# Sheet3.net
KiCad netlist of a schematic drawn in Altium Designer
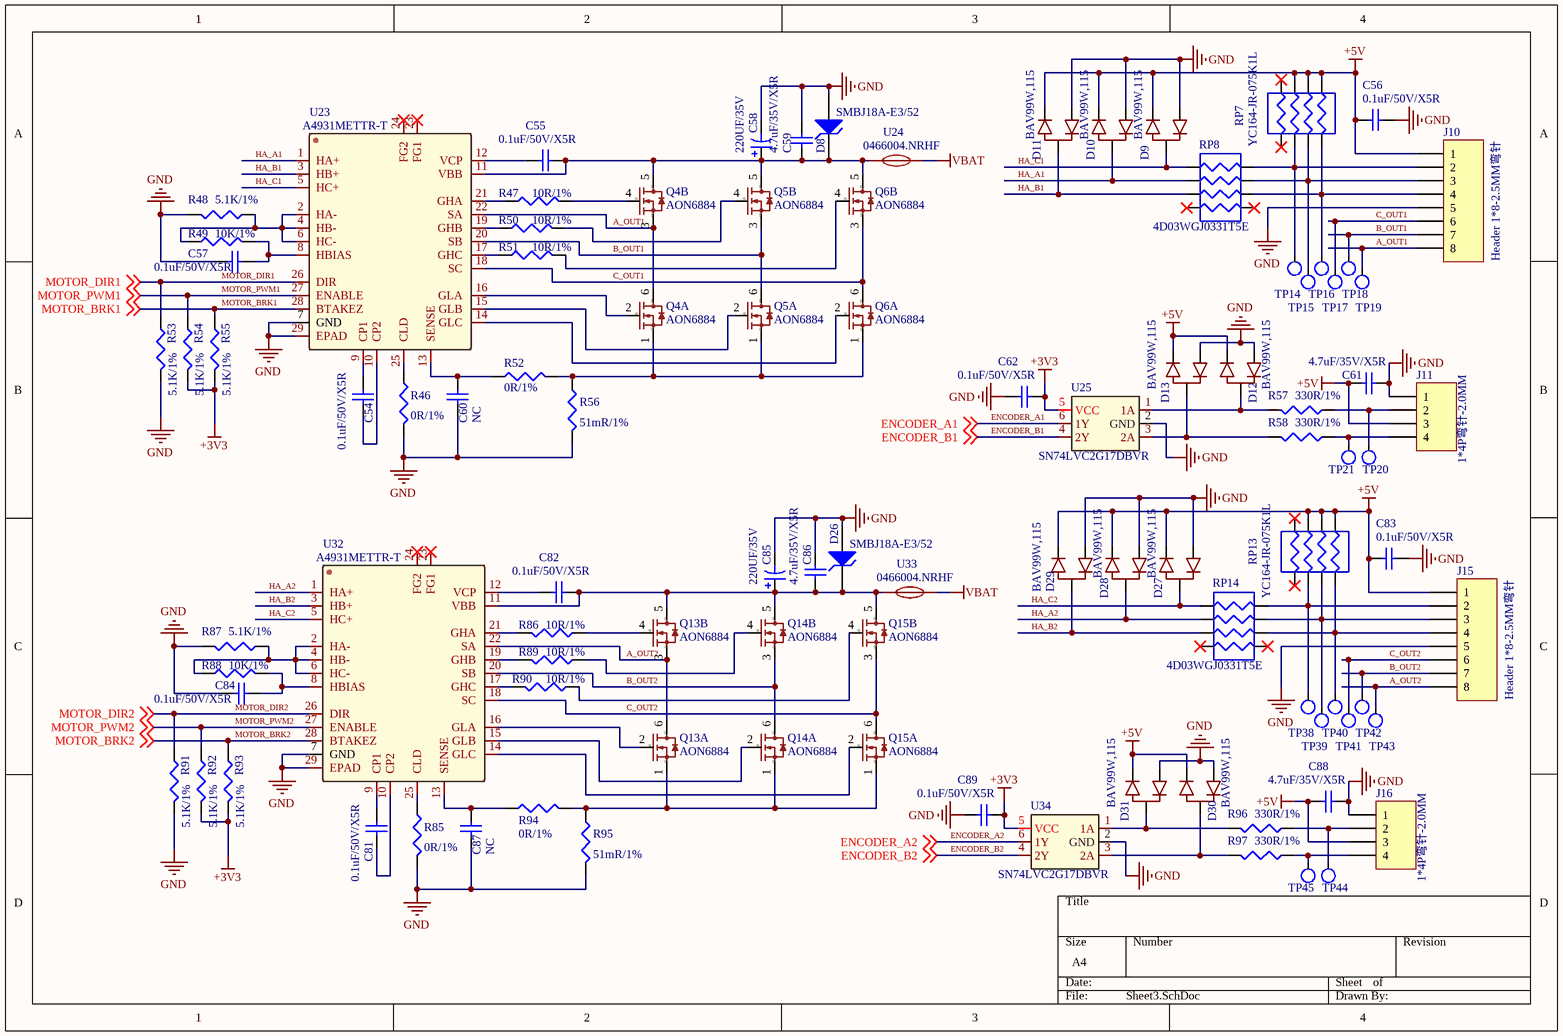
[diagram p0: Sheet3.SchDoc]

(export (version "E")
  (design (tool "Eeschema 10.0.6"))
  (components
    (comp (ref "C54")
      (value "0.1uF/50V/X5R")
      (footprint "C0603")
      (description "Capacitor (Semiconductor SIM Model)")
      (fields (field (name "PUBLISHER") "Altium Limited"))
      (libsource (lib "Miscellaneous Devices") (part "Cap Semi"))
    )
    (comp (ref "C55")
      (value "0.1uF/50V/X5R")
      (footprint "C0603")
      (description "Capacitor (Semiconductor SIM Model)")
      (fields (field (name "PUBLISHER") "Altium Limited"))
      (libsource (lib "Miscellaneous Devices") (part "Cap Semi"))
    )
    (comp (ref "C56")
      (value "0.1uF/50V/X5R")
      (footprint "C0603")
      (description "Capacitor (Semiconductor SIM Model)")
      (fields (field (name "PUBLISHER") "Altium Limited"))
      (libsource (lib "Miscellaneous Devices") (part "Cap Semi"))
    )
    (comp (ref "C57")
      (value "0.1uF/50V/X5R")
      (footprint "C0603")
      (description "Capacitor (Semiconductor SIM Model)")
      (fields (field (name "PUBLISHER") "Altium Limited"))
      (libsource (lib "Miscellaneous Devices") (part "Cap Semi"))
    )
    (comp (ref "C58")
      (value "220UF/35V")
      (footprint "SMD_8X10.2")
      (description "Polarized Capacitor (Radial)")
      (fields (field (name "PUBLISHER") "Altium Limited"))
      (libsource (lib "Miscellaneous Devices") (part "Cap Pol1"))
    )
    (comp (ref "C59")
      (value "4.7uF/35V/X5R")
      (footprint "C0805")
      (description "Capacitor (Semiconductor SIM Model)")
      (fields (field (name "PUBLISHER") "Altium Limited"))
      (libsource (lib "Miscellaneous Devices") (part "Cap Semi"))
    )
    (comp (ref "C60")
      (value "NC")
      (footprint "C0603")
      (description "Capacitor (Semiconductor SIM Model)")
      (fields (field (name "PUBLISHER") "Altium Limited"))
      (libsource (lib "Miscellaneous Devices") (part "Cap Semi"))
    )
    (comp (ref "C61")
      (value "4.7uF/35V/X5R")
      (footprint "C0603")
      (description "Capacitor (Semiconductor SIM Model)")
      (fields (field (name "PUBLISHER") "Altium Limited"))
      (libsource (lib "Miscellaneous Devices") (part "Cap Semi"))
    )
    (comp (ref "C62")
      (value "0.1uF/50V/X5R")
      (footprint "C0603")
      (description "Capacitor (Semiconductor SIM Model)")
      (fields (field (name "PUBLISHER") "Altium Limited"))
      (libsource (lib "Miscellaneous Devices") (part "Cap Semi"))
    )
    (comp (ref "C81")
      (value "0.1uF/50V/X5R")
      (footprint "C0603")
      (description "Capacitor (Semiconductor SIM Model)")
      (fields (field (name "PUBLISHER") "Altium Limited"))
      (libsource (lib "Miscellaneous Devices") (part "Cap Semi"))
    )
    (comp (ref "C82")
      (value "0.1uF/50V/X5R")
      (footprint "C0603")
      (description "Capacitor (Semiconductor SIM Model)")
      (fields (field (name "PUBLISHER") "Altium Limited"))
      (libsource (lib "Miscellaneous Devices") (part "Cap Semi"))
    )
    (comp (ref "C83")
      (value "0.1uF/50V/X5R")
      (footprint "C0603")
      (description "Capacitor (Semiconductor SIM Model)")
      (fields (field (name "PUBLISHER") "Altium Limited"))
      (libsource (lib "Miscellaneous Devices") (part "Cap Semi"))
    )
    (comp (ref "C84")
      (value "0.1uF/50V/X5R")
      (footprint "C0603")
      (description "Capacitor (Semiconductor SIM Model)")
      (fields (field (name "PUBLISHER") "Altium Limited"))
      (libsource (lib "Miscellaneous Devices") (part "Cap Semi"))
    )
    (comp (ref "C85")
      (value "220UF/35V")
      (footprint "SMD_8X10.2")
      (description "Polarized Capacitor (Radial)")
      (fields (field (name "PUBLISHER") "Altium Limited"))
      (libsource (lib "Miscellaneous Devices") (part "Cap Pol1"))
    )
    (comp (ref "C86")
      (value "4.7uF/35V/X5R")
      (footprint "C0805")
      (description "Capacitor (Semiconductor SIM Model)")
      (fields (field (name "PUBLISHER") "Altium Limited"))
      (libsource (lib "Miscellaneous Devices") (part "Cap Semi"))
    )
    (comp (ref "C87")
      (value "NC")
      (footprint "C0603")
      (description "Capacitor (Semiconductor SIM Model)")
      (fields (field (name "PUBLISHER") "Altium Limited"))
      (libsource (lib "Miscellaneous Devices") (part "Cap Semi"))
    )
    (comp (ref "C88")
      (value "4.7uF/35V/X5R")
      (footprint "C0603")
      (description "Capacitor (Semiconductor SIM Model)")
      (fields (field (name "PUBLISHER") "Altium Limited"))
      (libsource (lib "Miscellaneous Devices") (part "Cap Semi"))
    )
    (comp (ref "C89")
      (value "0.1uF/50V/X5R")
      (footprint "C0603")
      (description "Capacitor (Semiconductor SIM Model)")
      (fields (field (name "PUBLISHER") "Altium Limited"))
      (libsource (lib "Miscellaneous Devices") (part "Cap Semi"))
    )
    (comp (ref "D8")
      (value "SMBJ18A-E3/52")
      (footprint "SMB")
      (description "Zener Diode")
      (fields (field (name "PUBLISHER") "Altium Limited"))
      (libsource (lib "Miscellaneous Devices") (part "D Zener"))
    )
    (comp (ref "D9") (value "BAV99W,115") (libsource (lib "Schlib1") (part "BAV99W,115")))
    (comp (ref "D10") (value "BAV99W,115") (libsource (lib "Schlib1") (part "BAV99W,115")))
    (comp (ref "D11") (value "BAV99W,115") (libsource (lib "Schlib1") (part "BAV99W,115")))
    (comp (ref "D12") (value "BAV99W,115") (libsource (lib "Schlib1") (part "BAV99W,115")))
    (comp (ref "D13") (value "BAV99W,115") (libsource (lib "Schlib1") (part "BAV99W,115")))
    (comp (ref "D26")
      (value "SMBJ18A-E3/52")
      (footprint "SMB")
      (description "Zener Diode")
      (fields (field (name "PUBLISHER") "Altium Limited"))
      (libsource (lib "Miscellaneous Devices") (part "D Zener"))
    )
    (comp (ref "D27") (value "BAV99W,115") (libsource (lib "Schlib1") (part "BAV99W,115")))
    (comp (ref "D28") (value "BAV99W,115") (libsource (lib "Schlib1") (part "BAV99W,115")))
    (comp (ref "D29") (value "BAV99W,115") (libsource (lib "Schlib1") (part "BAV99W,115")))
    (comp (ref "D30") (value "BAV99W,115") (libsource (lib "Schlib1") (part "BAV99W,115")))
    (comp (ref "D31") (value "BAV99W,115") (libsource (lib "Schlib1") (part "BAV99W,115")))
    (comp (ref "J10")
      (value "Header 1*8-2.5MM弯针")
      (footprint "DIP_8X2.5")
      (description "Header, 8-Pin")
      (fields (field (name "PUBLISHER") "Altium Limited"))
      (libsource (lib "Miscellaneous Connectors") (part "Header 8"))
    )
    (comp (ref "J11")
      (value "1*4P弯针-2.0MM")
      (footprint "DIP_4X2MM")
      (description "Header, 4-Pin")
      (fields (field (name "PUBLISHER") "Altium Limited"))
      (libsource (lib "Miscellaneous Connectors") (part "Header 4"))
    )
    (comp (ref "J15")
      (value "Header 1*8-2.5MM弯针")
      (footprint "DIP_8X2.5")
      (description "Header, 8-Pin")
      (fields (field (name "PUBLISHER") "Altium Limited"))
      (libsource (lib "Miscellaneous Connectors") (part "Header 8"))
    )
    (comp (ref "J16")
      (value "1*4P弯针-2.0MM")
      (footprint "DIP_4X2MM")
      (description "Header, 4-Pin")
      (fields (field (name "PUBLISHER") "Altium Limited"))
      (libsource (lib "Miscellaneous Connectors") (part "Header 4"))
    )
    (comp (ref "Q4") (value "AON6884") (footprint "AOS") (libsource (lib "Schlib1") (part "AON6884")))
    (comp (ref "Q5") (value "AON6884") (footprint "AOS") (libsource (lib "Schlib1") (part "AON6884")))
    (comp (ref "Q6") (value "AON6884") (footprint "AOS") (libsource (lib "Schlib1") (part "AON6884")))
    (comp (ref "Q13") (value "AON6884") (footprint "AOS") (libsource (lib "Schlib1") (part "AON6884")))
    (comp (ref "Q14") (value "AON6884") (footprint "AOS") (libsource (lib "Schlib1") (part "AON6884")))
    (comp (ref "Q15") (value "AON6884") (footprint "AOS") (libsource (lib "Schlib1") (part "AON6884")))
    (comp (ref "R46")
      (value "0R/1%")
      (footprint "R0603")
      (description "Resistor")
      (fields (field (name "PUBLISHER") "Altium Limited"))
      (libsource (lib "Miscellaneous Devices") (part "Res3"))
    )
    (comp (ref "R47")
      (value "10R/1%")
      (footprint "R0603")
      (description "Resistor")
      (fields (field (name "PUBLISHER") "Altium Limited"))
      (libsource (lib "Miscellaneous Devices") (part "Res3"))
    )
    (comp (ref "R48")
      (value "5.1K/1%")
      (footprint "R0603")
      (description "Resistor")
      (fields (field (name "PUBLISHER") "Altium Limited"))
      (libsource (lib "Miscellaneous Devices") (part "Res3"))
    )
    (comp (ref "R49")
      (value "10K/1%")
      (footprint "R0603")
      (description "Resistor")
      (fields (field (name "PUBLISHER") "Altium Limited"))
      (libsource (lib "Miscellaneous Devices") (part "Res3"))
    )
    (comp (ref "R50")
      (value "10R/1%")
      (footprint "R0603")
      (description "Resistor")
      (fields (field (name "PUBLISHER") "Altium Limited"))
      (libsource (lib "Miscellaneous Devices") (part "Res3"))
    )
    (comp (ref "R51")
      (value "10R/1%")
      (footprint "R0603")
      (description "Resistor")
      (fields (field (name "PUBLISHER") "Altium Limited"))
      (libsource (lib "Miscellaneous Devices") (part "Res3"))
    )
    (comp (ref "R52")
      (value "0R/1%")
      (footprint "R0603")
      (description "Resistor")
      (fields (field (name "PUBLISHER") "Altium Limited"))
      (libsource (lib "Miscellaneous Devices") (part "Res3"))
    )
    (comp (ref "R53")
      (value "5.1K/1%")
      (footprint "R0603")
      (description "Resistor")
      (fields (field (name "PUBLISHER") "Altium Limited"))
      (libsource (lib "Miscellaneous Devices") (part "Res3"))
    )
    (comp (ref "R54")
      (value "5.1K/1%")
      (footprint "R0603")
      (description "Resistor")
      (fields (field (name "PUBLISHER") "Altium Limited"))
      (libsource (lib "Miscellaneous Devices") (part "Res3"))
    )
    (comp (ref "R55")
      (value "5.1K/1%")
      (footprint "R0603")
      (description "Resistor")
      (fields (field (name "PUBLISHER") "Altium Limited"))
      (libsource (lib "Miscellaneous Devices") (part "Res3"))
    )
    (comp (ref "R56")
      (value "51mR/1%")
      (footprint "R0805")
      (description "Resistor")
      (fields (field (name "PUBLISHER") "Altium Limited"))
      (libsource (lib "Miscellaneous Devices") (part "Res3"))
    )
    (comp (ref "R57")
      (value "330R/1%")
      (footprint "R0603")
      (description "Resistor")
      (fields (field (name "PUBLISHER") "Altium Limited"))
      (libsource (lib "Miscellaneous Devices") (part "Res3"))
    )
    (comp (ref "R58")
      (value "330R/1%")
      (footprint "R0603")
      (description "Resistor")
      (fields (field (name "PUBLISHER") "Altium Limited"))
      (libsource (lib "Miscellaneous Devices") (part "Res3"))
    )
    (comp (ref "R85")
      (value "0R/1%")
      (footprint "R0603")
      (description "Resistor")
      (fields (field (name "PUBLISHER") "Altium Limited"))
      (libsource (lib "Miscellaneous Devices") (part "Res3"))
    )
    (comp (ref "R86")
      (value "10R/1%")
      (footprint "R0603")
      (description "Resistor")
      (fields (field (name "PUBLISHER") "Altium Limited"))
      (libsource (lib "Miscellaneous Devices") (part "Res3"))
    )
    (comp (ref "R87")
      (value "5.1K/1%")
      (footprint "R0603")
      (description "Resistor")
      (fields (field (name "PUBLISHER") "Altium Limited"))
      (libsource (lib "Miscellaneous Devices") (part "Res3"))
    )
    (comp (ref "R88")
      (value "10K/1%")
      (footprint "R0603")
      (description "Resistor")
      (fields (field (name "PUBLISHER") "Altium Limited"))
      (libsource (lib "Miscellaneous Devices") (part "Res3"))
    )
    (comp (ref "R89")
      (value "10R/1%")
      (footprint "R0603")
      (description "Resistor")
      (fields (field (name "PUBLISHER") "Altium Limited"))
      (libsource (lib "Miscellaneous Devices") (part "Res3"))
    )
    (comp (ref "R90")
      (value "10R/1%")
      (footprint "R0603")
      (description "Resistor")
      (fields (field (name "PUBLISHER") "Altium Limited"))
      (libsource (lib "Miscellaneous Devices") (part "Res3"))
    )
    (comp (ref "R91")
      (value "5.1K/1%")
      (footprint "R0603")
      (description "Resistor")
      (fields (field (name "PUBLISHER") "Altium Limited"))
      (libsource (lib "Miscellaneous Devices") (part "Res3"))
    )
    (comp (ref "R92")
      (value "5.1K/1%")
      (footprint "R0603")
      (description "Resistor")
      (fields (field (name "PUBLISHER") "Altium Limited"))
      (libsource (lib "Miscellaneous Devices") (part "Res3"))
    )
    (comp (ref "R93")
      (value "5.1K/1%")
      (footprint "R0603")
      (description "Resistor")
      (fields (field (name "PUBLISHER") "Altium Limited"))
      (libsource (lib "Miscellaneous Devices") (part "Res3"))
    )
    (comp (ref "R94")
      (value "0R/1%")
      (footprint "R0603")
      (description "Resistor")
      (fields (field (name "PUBLISHER") "Altium Limited"))
      (libsource (lib "Miscellaneous Devices") (part "Res3"))
    )
    (comp (ref "R95")
      (value "51mR/1%")
      (footprint "R0805")
      (description "Resistor")
      (fields (field (name "PUBLISHER") "Altium Limited"))
      (libsource (lib "Miscellaneous Devices") (part "Res3"))
    )
    (comp (ref "R96")
      (value "330R/1%")
      (footprint "R0603")
      (description "Resistor")
      (fields (field (name "PUBLISHER") "Altium Limited"))
      (libsource (lib "Miscellaneous Devices") (part "Res3"))
    )
    (comp (ref "R97")
      (value "330R/1%")
      (footprint "R0603")
      (description "Resistor")
      (fields (field (name "PUBLISHER") "Altium Limited"))
      (libsource (lib "Miscellaneous Devices") (part "Res3"))
    )
    (comp (ref "RP7") (value "YC164-JR-075K1L") (footprint "RP-1206") (libsource (lib "Schlib1") (part "RP")))
    (comp (ref "RP8") (value "4D03WGJ0331T5E") (footprint "RP-1206") (libsource (lib "Schlib1") (part "RP")))
    (comp (ref "RP13")
      (value "YC164-JR-075K1L")
      (footprint "RP-1206")
      (libsource (lib "Schlib1") (part "RP"))
    )
    (comp (ref "RP14") (value "4D03WGJ0331T5E") (footprint "RP-1206") (libsource (lib "Schlib1") (part "RP")))
    (comp (ref "TP14") (value "TP") (footprint "TP") (libsource (lib "Schlib1") (part "TP")))
    (comp (ref "TP15") (value "TP") (footprint "TP") (libsource (lib "Schlib1") (part "TP")))
    (comp (ref "TP16") (value "TP") (footprint "TP") (libsource (lib "Schlib1") (part "TP")))
    (comp (ref "TP17") (value "TP") (footprint "TP") (libsource (lib "Schlib1") (part "TP")))
    (comp (ref "TP18") (value "TP") (footprint "TP") (libsource (lib "Schlib1") (part "TP")))
    (comp (ref "TP19") (value "TP") (footprint "TP") (libsource (lib "Schlib1") (part "TP")))
    (comp (ref "TP20") (value "TP") (footprint "TP") (libsource (lib "Schlib1") (part "TP")))
    (comp (ref "TP21") (value "TP") (footprint "TP") (libsource (lib "Schlib1") (part "TP")))
    (comp (ref "TP38") (value "TP") (footprint "TP") (libsource (lib "Schlib1") (part "TP")))
    (comp (ref "TP39") (value "TP") (footprint "TP") (libsource (lib "Schlib1") (part "TP")))
    (comp (ref "TP40") (value "TP") (footprint "TP") (libsource (lib "Schlib1") (part "TP")))
    (comp (ref "TP41") (value "TP") (footprint "TP") (libsource (lib "Schlib1") (part "TP")))
    (comp (ref "TP42") (value "TP") (footprint "TP") (libsource (lib "Schlib1") (part "TP")))
    (comp (ref "TP43") (value "TP") (footprint "TP") (libsource (lib "Schlib1") (part "TP")))
    (comp (ref "TP44") (value "TP") (footprint "TP") (libsource (lib "Schlib1") (part "TP")))
    (comp (ref "TP45") (value "TP") (footprint "TP") (libsource (lib "Schlib1") (part "TP")))
    (comp (ref "U23")
      (value "A4931METTR-T")
      (footprint "QFN-28")
      (libsource (lib "Schlib1") (part "A4931METTR-T"))
    )
    (comp (ref "U24")
      (value "0466004.NRHF")
      (footprint "1206")
      (libsource (lib "Schlib1") (part "0466004.NRHF"))
    )
    (comp (ref "U25")
      (value "SN74LVC2G17DBVR")
      (footprint "SOT-23-6")
      (libsource (lib "Schlib1") (part "SN74LVC2G17DBVR"))
    )
    (comp (ref "U32")
      (value "A4931METTR-T")
      (footprint "QFN-28")
      (libsource (lib "Schlib1") (part "A4931METTR-T"))
    )
    (comp (ref "U33")
      (value "0466004.NRHF")
      (footprint "1206")
      (libsource (lib "Schlib1") (part "0466004.NRHF"))
    )
    (comp (ref "U34")
      (value "SN74LVC2G17DBVR")
      (footprint "SOT-23-6")
      (libsource (lib "Schlib1") (part "SN74LVC2G17DBVR"))
    )
  )
  (nets
    (net (code "1") (name "+3V3") (class "Default")
      (node (ref "C62") (pin "1") (pinfunction "1_1") (pintype "passive"))
      (node (ref "C89") (pin "1") (pinfunction "1_1") (pintype "passive"))
      (node (ref "R54") (pin "2") (pinfunction "2_2") (pintype "passive"))
      (node (ref "R55") (pin "2") (pinfunction "2_2") (pintype "passive"))
      (node (ref "R92") (pin "2") (pinfunction "2_2") (pintype "passive"))
      (node (ref "R93") (pin "2") (pinfunction "2_2") (pintype "passive"))
      (node (ref "U25") (pin "5") (pinfunction "VCC_5") (pintype "passive"))
      (node (ref "U34") (pin "5") (pinfunction "VCC_5") (pintype "passive"))
    )
    (net (code "2") (name "+5V") (class "Default")
      (node (ref "C56") (pin "1") (pinfunction "1_1") (pintype "passive"))
      (node (ref "C61") (pin "2") (pinfunction "2_2") (pintype "passive"))
      (node (ref "C83") (pin "1") (pinfunction "1_1") (pintype "passive"))
      (node (ref "C88") (pin "1") (pinfunction "1_1") (pintype "passive"))
      (node (ref "D10") (pin "2") (pinfunction "2_2") (pintype "passive"))
      (node (ref "D11") (pin "2") (pinfunction "2_2") (pintype "passive"))
      (node (ref "D12") (pin "2") (pinfunction "2_2") (pintype "passive"))
      (node (ref "D13") (pin "2") (pinfunction "2_2") (pintype "passive"))
      (node (ref "D27") (pin "2") (pinfunction "2_2") (pintype "passive"))
      (node (ref "D28") (pin "2") (pinfunction "2_2") (pintype "passive"))
      (node (ref "D29") (pin "2") (pinfunction "2_2") (pintype "passive"))
      (node (ref "D30") (pin "2") (pinfunction "2_2") (pintype "passive"))
      (node (ref "D31") (pin "2") (pinfunction "2_2") (pintype "passive"))
      (node (ref "D9") (pin "2") (pinfunction "2_2") (pintype "passive"))
      (node (ref "J10") (pin "1") (pinfunction "1_1") (pintype "passive"))
      (node (ref "J11") (pin "3") (pinfunction "3_3") (pintype "passive"))
      (node (ref "J15") (pin "1") (pinfunction "1_1") (pintype "passive"))
      (node (ref "J16") (pin "3") (pinfunction "3_3") (pintype "passive"))
      (node (ref "RP13") (pin "1") (pinfunction "1_1") (pintype "passive"))
      (node (ref "RP13") (pin "2") (pinfunction "2_2") (pintype "passive"))
      (node (ref "RP13") (pin "3") (pinfunction "3_3") (pintype "passive"))
      (node (ref "RP7") (pin "1") (pinfunction "1_1") (pintype "passive"))
      (node (ref "RP7") (pin "2") (pinfunction "2_2") (pintype "passive"))
      (node (ref "RP7") (pin "3") (pinfunction "3_3") (pintype "passive"))
    )
    (net (code "3") (name "/A_OUT1") (class "Default")
      (node (ref "J10") (pin "8") (pinfunction "8_8") (pintype "passive"))
      (node (ref "Q4") (pin "3") (pinfunction "S_3") (pintype "passive"))
      (node (ref "Q4") (pin "6") (pinfunction "6_6") (pintype "passive"))
      (node (ref "TP19") (pin "1") (pinfunction "1_1") (pintype "passive"))
      (node (ref "U23") (pin "22") (pinfunction "SA_22") (pintype "passive"))
    )
    (net (code "4") (name "/A_OUT2") (class "Default")
      (node (ref "J15") (pin "8") (pinfunction "8_8") (pintype "passive"))
      (node (ref "Q13") (pin "3") (pinfunction "S_3") (pintype "passive"))
      (node (ref "Q13") (pin "6") (pinfunction "6_6") (pintype "passive"))
      (node (ref "TP43") (pin "1") (pinfunction "1_1") (pintype "passive"))
      (node (ref "U32") (pin "22") (pinfunction "SA_22") (pintype "passive"))
    )
    (net (code "5") (name "/B_OUT1") (class "Default")
      (node (ref "J10") (pin "7") (pinfunction "7_7") (pintype "passive"))
      (node (ref "Q5") (pin "3") (pinfunction "S_3") (pintype "passive"))
      (node (ref "Q5") (pin "6") (pinfunction "6_6") (pintype "passive"))
      (node (ref "TP18") (pin "1") (pinfunction "1_1") (pintype "passive"))
      (node (ref "U23") (pin "20") (pinfunction "SB_20") (pintype "passive"))
    )
    (net (code "6") (name "/B_OUT2") (class "Default")
      (node (ref "J15") (pin "7") (pinfunction "7_7") (pintype "passive"))
      (node (ref "Q14") (pin "3") (pinfunction "S_3") (pintype "passive"))
      (node (ref "Q14") (pin "6") (pinfunction "6_6") (pintype "passive"))
      (node (ref "TP42") (pin "1") (pinfunction "1_1") (pintype "passive"))
      (node (ref "U32") (pin "20") (pinfunction "SB_20") (pintype "passive"))
    )
    (net (code "7") (name "/C_OUT1") (class "Default")
      (node (ref "J10") (pin "6") (pinfunction "6_6") (pintype "passive"))
      (node (ref "Q6") (pin "3") (pinfunction "S_3") (pintype "passive"))
      (node (ref "Q6") (pin "6") (pinfunction "6_6") (pintype "passive"))
      (node (ref "TP17") (pin "1") (pinfunction "1_1") (pintype "passive"))
      (node (ref "U23") (pin "18") (pinfunction "SC_18") (pintype "passive"))
    )
    (net (code "8") (name "/C_OUT2") (class "Default")
      (node (ref "J15") (pin "6") (pinfunction "6_6") (pintype "passive"))
      (node (ref "Q15") (pin "3") (pinfunction "S_3") (pintype "passive"))
      (node (ref "Q15") (pin "6") (pinfunction "6_6") (pintype "passive"))
      (node (ref "TP41") (pin "1") (pinfunction "1_1") (pintype "passive"))
      (node (ref "U32") (pin "18") (pinfunction "SC_18") (pintype "passive"))
    )
    (net (code "9") (name "/HA_A1") (class "Default")
      (node (ref "D10") (pin "3") (pinfunction "3_3") (pintype "passive"))
      (node (ref "RP8") (pin "2") (pinfunction "2_2") (pintype "passive"))
      (node (ref "U23") (pin "1") (pinfunction "HA+_1") (pintype "passive"))
    )
    (net (code "10") (name "/HA_A2") (class "Default")
      (node (ref "D28") (pin "3") (pinfunction "3_3") (pintype "passive"))
      (node (ref "RP14") (pin "2") (pinfunction "2_2") (pintype "passive"))
      (node (ref "U32") (pin "1") (pinfunction "HA+_1") (pintype "passive"))
    )
    (net (code "11") (name "/HA_B1") (class "Default")
      (node (ref "D11") (pin "3") (pinfunction "3_3") (pintype "passive"))
      (node (ref "RP8") (pin "3") (pinfunction "3_3") (pintype "passive"))
      (node (ref "U23") (pin "3") (pinfunction "HB+_3") (pintype "passive"))
    )
    (net (code "12") (name "/HA_B2") (class "Default")
      (node (ref "D29") (pin "3") (pinfunction "3_3") (pintype "passive"))
      (node (ref "RP14") (pin "3") (pinfunction "3_3") (pintype "passive"))
      (node (ref "U32") (pin "3") (pinfunction "HB+_3") (pintype "passive"))
    )
    (net (code "13") (name "/HA_C1") (class "Default")
      (node (ref "D9") (pin "3") (pinfunction "3_3") (pintype "passive"))
      (node (ref "RP8") (pin "1") (pinfunction "1_1") (pintype "passive"))
      (node (ref "U23") (pin "5") (pinfunction "HC+_5") (pintype "passive"))
    )
    (net (code "14") (name "/HA_C2") (class "Default")
      (node (ref "D27") (pin "3") (pinfunction "3_3") (pintype "passive"))
      (node (ref "RP14") (pin "1") (pinfunction "1_1") (pintype "passive"))
      (node (ref "U32") (pin "5") (pinfunction "HC+_5") (pintype "passive"))
    )
    (net (code "15") (name "ENCODER_A1") (class "Default")
      (node (ref "U25") (pin "6") (pinfunction "1Y_6") (pintype "passive"))
    )
    (net (code "16") (name "ENCODER_A2") (class "Default")
      (node (ref "U34") (pin "6") (pinfunction "1Y_6") (pintype "passive"))
    )
    (net (code "17") (name "ENCODER_B1") (class "Default")
      (node (ref "U25") (pin "4") (pinfunction "2Y_4") (pintype "passive"))
    )
    (net (code "18") (name "ENCODER_B2") (class "Default")
      (node (ref "U34") (pin "4") (pinfunction "2Y_4") (pintype "passive"))
    )
    (net (code "19") (name "GND") (class "Default")
      (node (ref "C56") (pin "2") (pinfunction "2_2") (pintype "passive"))
      (node (ref "C57") (pin "2") (pinfunction "2_2") (pintype "passive"))
      (node (ref "C58") (pin "2") (pinfunction "2_2") (pintype "passive"))
      (node (ref "C59") (pin "2") (pinfunction "2_2") (pintype "passive"))
      (node (ref "C60") (pin "2") (pinfunction "2_2") (pintype "passive"))
      (node (ref "C61") (pin "1") (pinfunction "1_1") (pintype "passive"))
      (node (ref "C62") (pin "2") (pinfunction "2_2") (pintype "passive"))
      (node (ref "C83") (pin "2") (pinfunction "2_2") (pintype "passive"))
      (node (ref "C84") (pin "1") (pinfunction "1_1") (pintype "passive"))
      (node (ref "C85") (pin "2") (pinfunction "2_2") (pintype "passive"))
      (node (ref "C86") (pin "2") (pinfunction "2_2") (pintype "passive"))
      (node (ref "C87") (pin "2") (pinfunction "2_2") (pintype "passive"))
      (node (ref "C88") (pin "2") (pinfunction "2_2") (pintype "passive"))
      (node (ref "C89") (pin "2") (pinfunction "2_2") (pintype "passive"))
      (node (ref "D10") (pin "1") (pinfunction "1_1") (pintype "passive"))
      (node (ref "D11") (pin "1") (pinfunction "1_1") (pintype "passive"))
      (node (ref "D12") (pin "1") (pinfunction "1_1") (pintype "passive"))
      (node (ref "D13") (pin "1") (pinfunction "1_1") (pintype "passive"))
      (node (ref "D26") (pin "1") (pinfunction "A_1") (pintype "passive"))
      (node (ref "D27") (pin "1") (pinfunction "1_1") (pintype "passive"))
      (node (ref "D28") (pin "1") (pinfunction "1_1") (pintype "passive"))
      (node (ref "D29") (pin "1") (pinfunction "1_1") (pintype "passive"))
      (node (ref "D30") (pin "1") (pinfunction "1_1") (pintype "passive"))
      (node (ref "D31") (pin "1") (pinfunction "1_1") (pintype "passive"))
      (node (ref "D8") (pin "1") (pinfunction "A_1") (pintype "passive"))
      (node (ref "D9") (pin "1") (pinfunction "1_1") (pintype "passive"))
      (node (ref "J10") (pin "5") (pinfunction "5_5") (pintype "passive"))
      (node (ref "J11") (pin "1") (pinfunction "1_1") (pintype "passive"))
      (node (ref "J15") (pin "5") (pinfunction "5_5") (pintype "passive"))
      (node (ref "J16") (pin "1") (pinfunction "1_1") (pintype "passive"))
      (node (ref "R46") (pin "2") (pinfunction "2_2") (pintype "passive"))
      (node (ref "R48") (pin "2") (pinfunction "2_2") (pintype "passive"))
      (node (ref "R53") (pin "2") (pinfunction "2_2") (pintype "passive"))
      (node (ref "R56") (pin "2") (pinfunction "2_2") (pintype "passive"))
      (node (ref "R85") (pin "2") (pinfunction "2_2") (pintype "passive"))
      (node (ref "R87") (pin "2") (pinfunction "2_2") (pintype "passive"))
      (node (ref "R91") (pin "2") (pinfunction "2_2") (pintype "passive"))
      (node (ref "R95") (pin "2") (pinfunction "2_2") (pintype "passive"))
      (node (ref "U23") (pin "29") (pinfunction "EPAD_29") (pintype "passive"))
      (node (ref "U23") (pin "7") (pinfunction "GND_7") (pintype "passive"))
      (node (ref "U25") (pin "2") (pinfunction "GND_2") (pintype "passive"))
      (node (ref "U32") (pin "29") (pinfunction "EPAD_29") (pintype "passive"))
      (node (ref "U32") (pin "7") (pinfunction "GND_7") (pintype "passive"))
      (node (ref "U34") (pin "2") (pinfunction "GND_2") (pintype "passive"))
    )
    (net (code "20") (name "MOTOR_BRK1") (class "Default")
      (node (ref "R55") (pin "1") (pinfunction "1_1") (pintype "passive"))
      (node (ref "U23") (pin "28") (pinfunction "BTAKEZ_28") (pintype "passive"))
    )
    (net (code "21") (name "MOTOR_BRK2") (class "Default")
      (node (ref "R93") (pin "1") (pinfunction "1_1") (pintype "passive"))
      (node (ref "U32") (pin "28") (pinfunction "BTAKEZ_28") (pintype "passive"))
    )
    (net (code "22") (name "MOTOR_DIR1") (class "Default")
      (node (ref "R53") (pin "1") (pinfunction "1_1") (pintype "passive"))
      (node (ref "U23") (pin "26") (pinfunction "DIR_26") (pintype "passive"))
    )
    (net (code "23") (name "MOTOR_DIR2") (class "Default")
      (node (ref "R91") (pin "1") (pinfunction "1_1") (pintype "passive"))
      (node (ref "U32") (pin "26") (pinfunction "DIR_26") (pintype "passive"))
    )
    (net (code "24") (name "MOTOR_PWM1") (class "Default")
      (node (ref "R54") (pin "1") (pinfunction "1_1") (pintype "passive"))
      (node (ref "U23") (pin "27") (pinfunction "ENABLE_27") (pintype "passive"))
    )
    (net (code "25") (name "MOTOR_PWM2") (class "Default")
      (node (ref "R92") (pin "1") (pinfunction "1_1") (pintype "passive"))
      (node (ref "U32") (pin "27") (pinfunction "ENABLE_27") (pintype "passive"))
    )
    (net (code "26") (name "Net-(D8-K)") (class "Default")
      (node (ref "C55") (pin "2") (pinfunction "2_2") (pintype "passive"))
      (node (ref "C58") (pin "1") (pinfunction "1_1") (pintype "passive"))
      (node (ref "C59") (pin "1") (pinfunction "1_1") (pintype "passive"))
      (node (ref "D8") (pin "2") (pinfunction "K_2") (pintype "passive"))
      (node (ref "Q4") (pin "5") (pinfunction "D_5") (pintype "passive"))
      (node (ref "Q5") (pin "5") (pinfunction "D_5") (pintype "passive"))
      (node (ref "Q6") (pin "5") (pinfunction "D_5") (pintype "passive"))
      (node (ref "U23") (pin "11") (pinfunction "VBB_11") (pintype "passive"))
      (node (ref "U24") (pin "1") (pinfunction "1_1") (pintype "passive"))
    )
    (net (code "27") (name "Net-(D26-K)") (class "Default")
      (node (ref "C82") (pin "2") (pinfunction "2_2") (pintype "passive"))
      (node (ref "C85") (pin "1") (pinfunction "1_1") (pintype "passive"))
      (node (ref "C86") (pin "1") (pinfunction "1_1") (pintype "passive"))
      (node (ref "D26") (pin "2") (pinfunction "K_2") (pintype "passive"))
      (node (ref "Q13") (pin "5") (pinfunction "D_5") (pintype "passive"))
      (node (ref "Q14") (pin "5") (pinfunction "D_5") (pintype "passive"))
      (node (ref "Q15") (pin "5") (pinfunction "D_5") (pintype "passive"))
      (node (ref "U32") (pin "11") (pinfunction "VBB_11") (pintype "passive"))
      (node (ref "U33") (pin "1") (pinfunction "1_1") (pintype "passive"))
    )
    (net (code "28") (name "Net-(J10-Pad2)") (class "Default")
      (node (ref "J10") (pin "2") (pinfunction "2_2") (pintype "passive"))
      (node (ref "RP7") (pin "6") (pinfunction "6_6") (pintype "passive"))
      (node (ref "RP8") (pin "8") (pinfunction "8_8") (pintype "passive"))
      (node (ref "TP14") (pin "1") (pinfunction "1_1") (pintype "passive"))
    )
    (net (code "29") (name "Net-(J10-Pad3)") (class "Default")
      (node (ref "J10") (pin "3") (pinfunction "3_3") (pintype "passive"))
      (node (ref "RP7") (pin "7") (pinfunction "7_7") (pintype "passive"))
      (node (ref "RP8") (pin "7") (pinfunction "7_7") (pintype "passive"))
      (node (ref "TP15") (pin "1") (pinfunction "1_1") (pintype "passive"))
    )
    (net (code "30") (name "Net-(J10-Pad4)") (class "Default")
      (node (ref "J10") (pin "4") (pinfunction "4_4") (pintype "passive"))
      (node (ref "RP7") (pin "8") (pinfunction "8_8") (pintype "passive"))
      (node (ref "RP8") (pin "6") (pinfunction "6_6") (pintype "passive"))
      (node (ref "TP16") (pin "1") (pinfunction "1_1") (pintype "passive"))
    )
    (net (code "31") (name "Net-(J11-Pad2)") (class "Default")
      (node (ref "J11") (pin "2") (pinfunction "2_2") (pintype "passive"))
      (node (ref "R57") (pin "1") (pinfunction "1_1") (pintype "passive"))
      (node (ref "TP20") (pin "1") (pinfunction "1_1") (pintype "passive"))
    )
    (net (code "32") (name "Net-(J11-Pad4)") (class "Default")
      (node (ref "J11") (pin "4") (pinfunction "4_4") (pintype "passive"))
      (node (ref "R58") (pin "1") (pinfunction "1_1") (pintype "passive"))
      (node (ref "TP21") (pin "1") (pinfunction "1_1") (pintype "passive"))
    )
    (net (code "33") (name "Net-(J15-Pad2)") (class "Default")
      (node (ref "J15") (pin "2") (pinfunction "2_2") (pintype "passive"))
      (node (ref "RP13") (pin "6") (pinfunction "6_6") (pintype "passive"))
      (node (ref "RP14") (pin "8") (pinfunction "8_8") (pintype "passive"))
      (node (ref "TP38") (pin "1") (pinfunction "1_1") (pintype "passive"))
    )
    (net (code "34") (name "Net-(J15-Pad3)") (class "Default")
      (node (ref "J15") (pin "3") (pinfunction "3_3") (pintype "passive"))
      (node (ref "RP13") (pin "7") (pinfunction "7_7") (pintype "passive"))
      (node (ref "RP14") (pin "7") (pinfunction "7_7") (pintype "passive"))
      (node (ref "TP39") (pin "1") (pinfunction "1_1") (pintype "passive"))
    )
    (net (code "35") (name "Net-(J15-Pad4)") (class "Default")
      (node (ref "J15") (pin "4") (pinfunction "4_4") (pintype "passive"))
      (node (ref "RP13") (pin "8") (pinfunction "8_8") (pintype "passive"))
      (node (ref "RP14") (pin "6") (pinfunction "6_6") (pintype "passive"))
      (node (ref "TP40") (pin "1") (pinfunction "1_1") (pintype "passive"))
    )
    (net (code "36") (name "Net-(J16-Pad2)") (class "Default")
      (node (ref "J16") (pin "2") (pinfunction "2_2") (pintype "passive"))
      (node (ref "R96") (pin "1") (pinfunction "1_1") (pintype "passive"))
      (node (ref "TP44") (pin "1") (pinfunction "1_1") (pintype "passive"))
    )
    (net (code "37") (name "Net-(J16-Pad4)") (class "Default")
      (node (ref "J16") (pin "4") (pinfunction "4_4") (pintype "passive"))
      (node (ref "R97") (pin "1") (pinfunction "1_1") (pintype "passive"))
      (node (ref "TP45") (pin "1") (pinfunction "1_1") (pintype "passive"))
    )
    (net (code "38") (name "Net-(Q4A-G)") (class "Default")
      (node (ref "Q4") (pin "2") (pinfunction "G_2") (pintype "passive"))
      (node (ref "U23") (pin "16") (pinfunction "GLA_16") (pintype "passive"))
    )
    (net (code "39") (name "Net-(Q4A-S)") (class "Default")
      (node (ref "Q4") (pin "1") (pinfunction "S_1") (pintype "passive"))
      (node (ref "Q5") (pin "1") (pinfunction "S_1") (pintype "passive"))
      (node (ref "Q6") (pin "1") (pinfunction "S_1") (pintype "passive"))
      (node (ref "R52") (pin "2") (pinfunction "2_2") (pintype "passive"))
      (node (ref "R56") (pin "1") (pinfunction "1_1") (pintype "passive"))
    )
    (net (code "40") (name "Net-(Q4B-G)") (class "Default")
      (node (ref "Q4") (pin "4") (pinfunction "G_4") (pintype "passive"))
      (node (ref "R47") (pin "2") (pinfunction "2_2") (pintype "passive"))
    )
    (net (code "41") (name "Net-(Q5A-G)") (class "Default")
      (node (ref "Q5") (pin "2") (pinfunction "G_2") (pintype "passive"))
      (node (ref "U23") (pin "15") (pinfunction "GLB_15") (pintype "passive"))
    )
    (net (code "42") (name "Net-(Q5B-G)") (class "Default")
      (node (ref "Q5") (pin "4") (pinfunction "G_4") (pintype "passive"))
      (node (ref "R50") (pin "2") (pinfunction "2_2") (pintype "passive"))
    )
    (net (code "43") (name "Net-(Q6A-G)") (class "Default")
      (node (ref "Q6") (pin "2") (pinfunction "G_2") (pintype "passive"))
      (node (ref "U23") (pin "14") (pinfunction "GLC_14") (pintype "passive"))
    )
    (net (code "44") (name "Net-(Q6B-G)") (class "Default")
      (node (ref "Q6") (pin "4") (pinfunction "G_4") (pintype "passive"))
      (node (ref "R51") (pin "2") (pinfunction "2_2") (pintype "passive"))
    )
    (net (code "45") (name "Net-(Q13A-G)") (class "Default")
      (node (ref "Q13") (pin "2") (pinfunction "G_2") (pintype "passive"))
      (node (ref "U32") (pin "16") (pinfunction "GLA_16") (pintype "passive"))
    )
    (net (code "46") (name "Net-(Q13A-S)") (class "Default")
      (node (ref "Q13") (pin "1") (pinfunction "S_1") (pintype "passive"))
      (node (ref "Q14") (pin "1") (pinfunction "S_1") (pintype "passive"))
      (node (ref "Q15") (pin "1") (pinfunction "S_1") (pintype "passive"))
      (node (ref "R94") (pin "2") (pinfunction "2_2") (pintype "passive"))
      (node (ref "R95") (pin "1") (pinfunction "1_1") (pintype "passive"))
    )
    (net (code "47") (name "Net-(Q13B-G)") (class "Default")
      (node (ref "Q13") (pin "4") (pinfunction "G_4") (pintype "passive"))
      (node (ref "R86") (pin "1") (pinfunction "1_1") (pintype "passive"))
    )
    (net (code "48") (name "Net-(Q14A-G)") (class "Default")
      (node (ref "Q14") (pin "2") (pinfunction "G_2") (pintype "passive"))
      (node (ref "U32") (pin "15") (pinfunction "GLB_15") (pintype "passive"))
    )
    (net (code "49") (name "Net-(Q14B-G)") (class "Default")
      (node (ref "Q14") (pin "4") (pinfunction "G_4") (pintype "passive"))
      (node (ref "R89") (pin "1") (pinfunction "1_1") (pintype "passive"))
    )
    (net (code "50") (name "Net-(Q15A-G)") (class "Default")
      (node (ref "Q15") (pin "2") (pinfunction "G_2") (pintype "passive"))
      (node (ref "U32") (pin "14") (pinfunction "GLC_14") (pintype "passive"))
    )
    (net (code "51") (name "Net-(Q15B-G)") (class "Default")
      (node (ref "Q15") (pin "4") (pinfunction "G_4") (pintype "passive"))
      (node (ref "R90") (pin "1") (pinfunction "1_1") (pintype "passive"))
    )
    (net (code "52") (name "Net-(U23-CLD)") (class "Default")
      (node (ref "R46") (pin "1") (pinfunction "1_1") (pintype "passive"))
      (node (ref "U23") (pin "25") (pinfunction "CLD_25") (pintype "passive"))
    )
    (net (code "53") (name "Net-(U23-CP1)") (class "Default")
      (node (ref "C54") (pin "1") (pinfunction "1_1") (pintype "passive"))
      (node (ref "U23") (pin "9") (pinfunction "CP1_9") (pintype "passive"))
    )
    (net (code "54") (name "Net-(U23-CP2)") (class "Default")
      (node (ref "C54") (pin "2") (pinfunction "2_2") (pintype "passive"))
      (node (ref "U23") (pin "10") (pinfunction "CP2_10") (pintype "passive"))
    )
    (net (code "55") (name "Net-(U23-GHA)") (class "Default")
      (node (ref "R47") (pin "1") (pinfunction "1_1") (pintype "passive"))
      (node (ref "U23") (pin "21") (pinfunction "GHA_21") (pintype "passive"))
    )
    (net (code "56") (name "Net-(U23-GHB)") (class "Default")
      (node (ref "R50") (pin "1") (pinfunction "1_1") (pintype "passive"))
      (node (ref "U23") (pin "19") (pinfunction "GHB_19") (pintype "passive"))
    )
    (net (code "57") (name "Net-(U23-GHC)") (class "Default")
      (node (ref "R51") (pin "1") (pinfunction "1_1") (pintype "passive"))
      (node (ref "U23") (pin "17") (pinfunction "GHC_17") (pintype "passive"))
    )
    (net (code "58") (name "Net-(U23-HA-)") (class "Default")
      (node (ref "R48") (pin "1") (pinfunction "1_1") (pintype "passive"))
      (node (ref "R49") (pin "1") (pinfunction "1_1") (pintype "passive"))
      (node (ref "U23") (pin "2") (pinfunction "HA-_2") (pintype "passive"))
      (node (ref "U23") (pin "4") (pinfunction "HB-_4") (pintype "passive"))
      (node (ref "U23") (pin "6") (pinfunction "HC-_6") (pintype "passive"))
    )
    (net (code "59") (name "Net-(U23-HBIAS)") (class "Default")
      (node (ref "C57") (pin "1") (pinfunction "1_1") (pintype "passive"))
      (node (ref "R49") (pin "2") (pinfunction "2_2") (pintype "passive"))
      (node (ref "U23") (pin "8") (pinfunction "HBIAS_8") (pintype "passive"))
    )
    (net (code "60") (name "Net-(U23-SENSE)") (class "Default")
      (node (ref "C60") (pin "1") (pinfunction "1_1") (pintype "passive"))
      (node (ref "R52") (pin "1") (pinfunction "1_1") (pintype "passive"))
      (node (ref "U23") (pin "13") (pinfunction "SENSE_13") (pintype "passive"))
    )
    (net (code "61") (name "Net-(U23-VCP)") (class "Default")
      (node (ref "C55") (pin "1") (pinfunction "1_1") (pintype "passive"))
      (node (ref "U23") (pin "12") (pinfunction "VCP_12") (pintype "passive"))
    )
    (net (code "62") (name "Net-(U25-1A)") (class "Default")
      (node (ref "D12") (pin "3") (pinfunction "3_3") (pintype "passive"))
      (node (ref "R57") (pin "2") (pinfunction "2_2") (pintype "passive"))
      (node (ref "U25") (pin "1") (pinfunction "1A_1") (pintype "passive"))
    )
    (net (code "63") (name "Net-(U25-2A)") (class "Default")
      (node (ref "D13") (pin "3") (pinfunction "3_3") (pintype "passive"))
      (node (ref "R58") (pin "2") (pinfunction "2_2") (pintype "passive"))
      (node (ref "U25") (pin "3") (pinfunction "2A_3") (pintype "passive"))
    )
    (net (code "64") (name "Net-(U32-CLD)") (class "Default")
      (node (ref "R85") (pin "1") (pinfunction "1_1") (pintype "passive"))
      (node (ref "U32") (pin "25") (pinfunction "CLD_25") (pintype "passive"))
    )
    (net (code "65") (name "Net-(U32-CP1)") (class "Default")
      (node (ref "C81") (pin "1") (pinfunction "1_1") (pintype "passive"))
      (node (ref "U32") (pin "9") (pinfunction "CP1_9") (pintype "passive"))
    )
    (net (code "66") (name "Net-(U32-CP2)") (class "Default")
      (node (ref "C81") (pin "2") (pinfunction "2_2") (pintype "passive"))
      (node (ref "U32") (pin "10") (pinfunction "CP2_10") (pintype "passive"))
    )
    (net (code "67") (name "Net-(U32-GHA)") (class "Default")
      (node (ref "R86") (pin "2") (pinfunction "2_2") (pintype "passive"))
      (node (ref "U32") (pin "21") (pinfunction "GHA_21") (pintype "passive"))
    )
    (net (code "68") (name "Net-(U32-GHB)") (class "Default")
      (node (ref "R89") (pin "2") (pinfunction "2_2") (pintype "passive"))
      (node (ref "U32") (pin "19") (pinfunction "GHB_19") (pintype "passive"))
    )
    (net (code "69") (name "Net-(U32-GHC)") (class "Default")
      (node (ref "R90") (pin "2") (pinfunction "2_2") (pintype "passive"))
      (node (ref "U32") (pin "17") (pinfunction "GHC_17") (pintype "passive"))
    )
    (net (code "70") (name "Net-(U32-HA-)") (class "Default")
      (node (ref "R87") (pin "1") (pinfunction "1_1") (pintype "passive"))
      (node (ref "R88") (pin "1") (pinfunction "1_1") (pintype "passive"))
      (node (ref "U32") (pin "2") (pinfunction "HA-_2") (pintype "passive"))
      (node (ref "U32") (pin "4") (pinfunction "HB-_4") (pintype "passive"))
      (node (ref "U32") (pin "6") (pinfunction "HC-_6") (pintype "passive"))
    )
    (net (code "71") (name "Net-(U32-HBIAS)") (class "Default")
      (node (ref "C84") (pin "2") (pinfunction "2_2") (pintype "passive"))
      (node (ref "R88") (pin "2") (pinfunction "2_2") (pintype "passive"))
      (node (ref "U32") (pin "8") (pinfunction "HBIAS_8") (pintype "passive"))
    )
    (net (code "72") (name "Net-(U32-SENSE)") (class "Default")
      (node (ref "C87") (pin "1") (pinfunction "1_1") (pintype "passive"))
      (node (ref "R94") (pin "1") (pinfunction "1_1") (pintype "passive"))
      (node (ref "U32") (pin "13") (pinfunction "SENSE_13") (pintype "passive"))
    )
    (net (code "73") (name "Net-(U32-VCP)") (class "Default")
      (node (ref "C82") (pin "1") (pinfunction "1_1") (pintype "passive"))
      (node (ref "U32") (pin "12") (pinfunction "VCP_12") (pintype "passive"))
    )
    (net (code "74") (name "Net-(U34-1A)") (class "Default")
      (node (ref "D31") (pin "3") (pinfunction "3_3") (pintype "passive"))
      (node (ref "R96") (pin "2") (pinfunction "2_2") (pintype "passive"))
      (node (ref "U34") (pin "1") (pinfunction "1A_1") (pintype "passive"))
    )
    (net (code "75") (name "Net-(U34-2A)") (class "Default")
      (node (ref "D30") (pin "3") (pinfunction "3_3") (pintype "passive"))
      (node (ref "R97") (pin "2") (pinfunction "2_2") (pintype "passive"))
      (node (ref "U34") (pin "3") (pinfunction "2A_3") (pintype "passive"))
    )
    (net (code "76") (name "VBAT") (class "Default")
      (node (ref "U24") (pin "2") (pinfunction "2_2") (pintype "passive"))
      (node (ref "U33") (pin "2") (pinfunction "2_2") (pintype "passive"))
    )
    (net (code "77") (name "unconnected-(RP7-Pad4)") (class "Default")
      (node (ref "RP7") (pin "4") (pinfunction "4_4") (pintype "passive+no_connect"))
    )
    (net (code "78") (name "unconnected-(RP7-Pad5)") (class "Default")
      (node (ref "RP7") (pin "5") (pinfunction "5_5") (pintype "passive+no_connect"))
    )
    (net (code "79") (name "unconnected-(RP8-Pad4)") (class "Default")
      (node (ref "RP8") (pin "4") (pinfunction "4_4") (pintype "passive+no_connect"))
    )
    (net (code "80") (name "unconnected-(RP8-Pad5)") (class "Default")
      (node (ref "RP8") (pin "5") (pinfunction "5_5") (pintype "passive+no_connect"))
    )
    (net (code "81") (name "unconnected-(RP13-Pad4)") (class "Default")
      (node (ref "RP13") (pin "4") (pinfunction "4_4") (pintype "passive+no_connect"))
    )
    (net (code "82") (name "unconnected-(RP13-Pad5)") (class "Default")
      (node (ref "RP13") (pin "5") (pinfunction "5_5") (pintype "passive+no_connect"))
    )
    (net (code "83") (name "unconnected-(RP14-Pad4)") (class "Default")
      (node (ref "RP14") (pin "4") (pinfunction "4_4") (pintype "passive+no_connect"))
    )
    (net (code "84") (name "unconnected-(RP14-Pad5)") (class "Default")
      (node (ref "RP14") (pin "5") (pinfunction "5_5") (pintype "passive+no_connect"))
    )
    (net (code "85") (name "unconnected-(U23-FG1-Pad23)") (class "Default")
      (node (ref "U23") (pin "23") (pinfunction "FG1_23") (pintype "passive+no_connect"))
    )
    (net (code "86") (name "unconnected-(U23-FG2-Pad24)") (class "Default")
      (node (ref "U23") (pin "24") (pinfunction "FG2_24") (pintype "passive+no_connect"))
    )
    (net (code "87") (name "unconnected-(U32-FG1-Pad23)") (class "Default")
      (node (ref "U32") (pin "23") (pinfunction "FG1_23") (pintype "passive+no_connect"))
    )
    (net (code "88") (name "unconnected-(U32-FG2-Pad24)") (class "Default")
      (node (ref "U32") (pin "24") (pinfunction "FG2_24") (pintype "passive+no_connect"))
    )
  )
)
